# T4p1_fpc_adapter.net
KiCad netlist of a schematic drawn in EAGLE
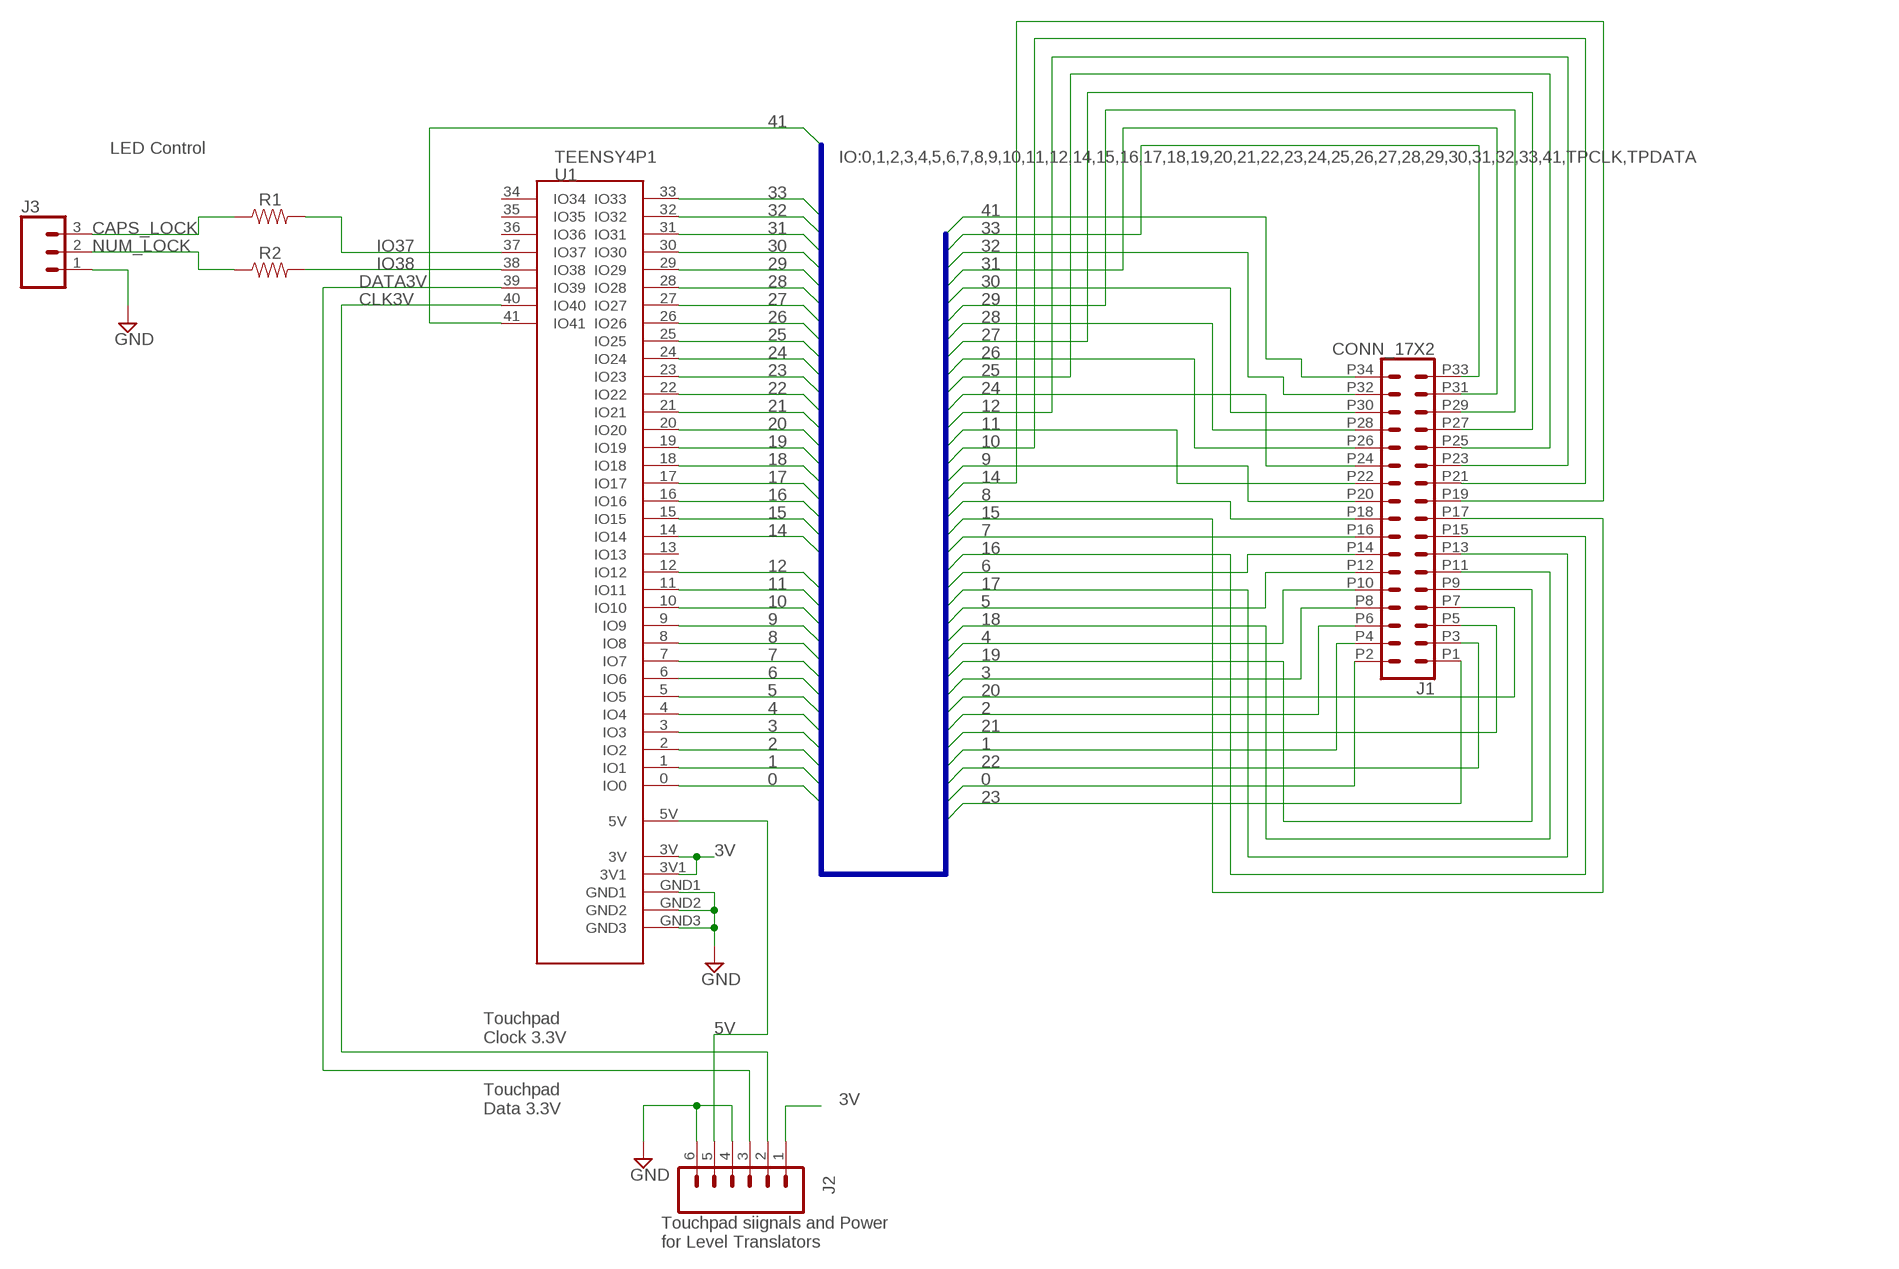
[diagram p0: schematic, sheet 1]

(export (version "E")
  (design (tool "Eeschema 10.0.6"))
  (components
    (comp (ref "J1")
      (value "CONN_17X2")
      (footprint "eagle-import:2X17")
      (libsource (lib "eagle-import") (part "CONN_17X2"))
    )
    (comp (ref "J2")
      (value "CONN_06NO_SILK_FEMALE_PTH")
      (footprint "eagle-import:1X06_NO_SILK")
      (libsource (lib "eagle-import") (part "CONN_06NO_SILK_FEMALE_PTH"))
    )
    (comp (ref "J3")
      (value "CONN_031X03_NO_SILK")
      (footprint "eagle-import:1X03_NO_SILK")
      (libsource (lib "eagle-import") (part "CONN_031X03_NO_SILK"))
    )
    (comp (ref "R1")
      (value "RESISTOR_AXIAL")
      (footprint "eagle-import:AXIAL-0.3")
      (libsource (lib "eagle-import") (part "RESISTOR_AXIAL"))
    )
    (comp (ref "R2")
      (value "RESISTOR_AXIAL")
      (footprint "eagle-import:AXIAL-0.3")
      (libsource (lib "eagle-import") (part "RESISTOR_AXIAL"))
    )
    (comp (ref "U1")
      (value "TEENSY4P1")
      (footprint "eagle-import:TEENSY4P1")
      (libsource (lib "eagle-import") (part "TEENSYP41"))
    )
  )
  (nets
    (net (code "4") (name "/0") (class "Default")
      (node (ref "J1") (pin "P2") (pinfunction "2_P2") (pintype "passive"))
      (node (ref "U1") (pin "0") (pinfunction "IO0_0") (pintype "bidirectional"))
    )
    (net (code "5") (name "/1") (class "Default")
      (node (ref "J1") (pin "P4") (pinfunction "4_P4") (pintype "passive"))
      (node (ref "U1") (pin "1") (pinfunction "IO1_1") (pintype "bidirectional"))
    )
    (net (code "6") (name "/2") (class "Default")
      (node (ref "J1") (pin "P6") (pinfunction "6_P6") (pintype "passive"))
      (node (ref "U1") (pin "2") (pinfunction "IO2_2") (pintype "bidirectional"))
    )
    (net (code "7") (name "/3") (class "Default")
      (node (ref "J1") (pin "P8") (pinfunction "8_P8") (pintype "passive"))
      (node (ref "U1") (pin "3") (pinfunction "IO3_3") (pintype "bidirectional"))
    )
    (net (code "8") (name "/3V") (class "Default")
      (node (ref "J2") (pin "1") (pinfunction "1_1") (pintype "passive"))
      (node (ref "U1") (pin "3V") (pinfunction "3V_3V") (pintype "bidirectional"))
      (node (ref "U1") (pin "3V1") (pinfunction "3V1_3V1") (pintype "bidirectional"))
    )
    (net (code "9") (name "/4") (class "Default")
      (node (ref "J1") (pin "P10") (pinfunction "10_P10") (pintype "passive"))
      (node (ref "U1") (pin "4") (pinfunction "IO4_4") (pintype "bidirectional"))
    )
    (net (code "10") (name "/5") (class "Default")
      (node (ref "J1") (pin "P12") (pinfunction "12_P12") (pintype "passive"))
      (node (ref "U1") (pin "5") (pinfunction "IO5_5") (pintype "bidirectional"))
    )
    (net (code "11") (name "/5V") (class "Default")
      (node (ref "J2") (pin "5") (pinfunction "5_5") (pintype "passive"))
      (node (ref "U1") (pin "5V") (pinfunction "5V_5V") (pintype "bidirectional"))
    )
    (net (code "12") (name "/6") (class "Default")
      (node (ref "J1") (pin "P14") (pinfunction "14_P14") (pintype "passive"))
      (node (ref "U1") (pin "6") (pinfunction "IO6_6") (pintype "bidirectional"))
    )
    (net (code "13") (name "/7") (class "Default")
      (node (ref "J1") (pin "P16") (pinfunction "16_P16") (pintype "passive"))
      (node (ref "U1") (pin "7") (pinfunction "IO7_7") (pintype "bidirectional"))
    )
    (net (code "14") (name "/8") (class "Default")
      (node (ref "J1") (pin "P18") (pinfunction "18_P18") (pintype "passive"))
      (node (ref "U1") (pin "8") (pinfunction "IO8_8") (pintype "bidirectional"))
    )
    (net (code "15") (name "/9") (class "Default")
      (node (ref "J1") (pin "P20") (pinfunction "20_P20") (pintype "passive"))
      (node (ref "U1") (pin "9") (pinfunction "IO9_9") (pintype "bidirectional"))
    )
    (net (code "16") (name "/10") (class "Default")
      (node (ref "J1") (pin "P21") (pinfunction "21_P21") (pintype "passive"))
      (node (ref "U1") (pin "10") (pinfunction "IO10_10") (pintype "bidirectional"))
    )
    (net (code "17") (name "/11") (class "Default")
      (node (ref "J1") (pin "P22") (pinfunction "22_P22") (pintype "passive"))
      (node (ref "U1") (pin "11") (pinfunction "IO11_11") (pintype "bidirectional"))
    )
    (net (code "18") (name "/12") (class "Default")
      (node (ref "J1") (pin "P23") (pinfunction "23_P23") (pintype "passive"))
      (node (ref "U1") (pin "12") (pinfunction "IO12_12") (pintype "bidirectional"))
    )
    (net (code "19") (name "/14") (class "Default")
      (node (ref "J1") (pin "P19") (pinfunction "19_P19") (pintype "passive"))
      (node (ref "U1") (pin "14") (pinfunction "IO14_14") (pintype "bidirectional"))
    )
    (net (code "20") (name "/15") (class "Default")
      (node (ref "J1") (pin "P17") (pinfunction "17_P17") (pintype "passive"))
      (node (ref "U1") (pin "15") (pinfunction "IO15_15") (pintype "bidirectional"))
    )
    (net (code "21") (name "/16") (class "Default")
      (node (ref "J1") (pin "P15") (pinfunction "15_P15") (pintype "passive"))
      (node (ref "U1") (pin "16") (pinfunction "IO16_16") (pintype "bidirectional"))
    )
    (net (code "22") (name "/17") (class "Default")
      (node (ref "J1") (pin "P13") (pinfunction "13_P13") (pintype "passive"))
      (node (ref "U1") (pin "17") (pinfunction "IO17_17") (pintype "bidirectional"))
    )
    (net (code "23") (name "/18") (class "Default")
      (node (ref "J1") (pin "P11") (pinfunction "11_P11") (pintype "passive"))
      (node (ref "U1") (pin "18") (pinfunction "IO18_18") (pintype "bidirectional"))
    )
    (net (code "24") (name "/19") (class "Default")
      (node (ref "J1") (pin "P9") (pinfunction "9_P9") (pintype "passive"))
      (node (ref "U1") (pin "19") (pinfunction "IO19_19") (pintype "bidirectional"))
    )
    (net (code "25") (name "/20") (class "Default")
      (node (ref "J1") (pin "P7") (pinfunction "7_P7") (pintype "passive"))
      (node (ref "U1") (pin "20") (pinfunction "IO20_20") (pintype "bidirectional"))
    )
    (net (code "26") (name "/21") (class "Default")
      (node (ref "J1") (pin "P5") (pinfunction "5_P5") (pintype "passive"))
      (node (ref "U1") (pin "21") (pinfunction "IO21_21") (pintype "bidirectional"))
    )
    (net (code "27") (name "/22") (class "Default")
      (node (ref "J1") (pin "P3") (pinfunction "3_P3") (pintype "passive"))
      (node (ref "U1") (pin "22") (pinfunction "IO22_22") (pintype "bidirectional"))
    )
    (net (code "28") (name "/23") (class "Default")
      (node (ref "J1") (pin "P1") (pinfunction "1_P1") (pintype "passive"))
      (node (ref "U1") (pin "23") (pinfunction "IO23_23") (pintype "bidirectional"))
    )
    (net (code "29") (name "/24") (class "Default")
      (node (ref "J1") (pin "P24") (pinfunction "24_P24") (pintype "passive"))
      (node (ref "U1") (pin "24") (pinfunction "IO24_24") (pintype "bidirectional"))
    )
    (net (code "30") (name "/25") (class "Default")
      (node (ref "J1") (pin "P25") (pinfunction "25_P25") (pintype "passive"))
      (node (ref "U1") (pin "25") (pinfunction "IO25_25") (pintype "bidirectional"))
    )
    (net (code "31") (name "/26") (class "Default")
      (node (ref "J1") (pin "P26") (pinfunction "26_P26") (pintype "passive"))
      (node (ref "U1") (pin "26") (pinfunction "IO26_26") (pintype "bidirectional"))
    )
    (net (code "32") (name "/27") (class "Default")
      (node (ref "J1") (pin "P27") (pinfunction "27_P27") (pintype "passive"))
      (node (ref "U1") (pin "27") (pinfunction "IO27_27") (pintype "bidirectional"))
    )
    (net (code "33") (name "/28") (class "Default")
      (node (ref "J1") (pin "P28") (pinfunction "28_P28") (pintype "passive"))
      (node (ref "U1") (pin "28") (pinfunction "IO28_28") (pintype "bidirectional"))
    )
    (net (code "34") (name "/29") (class "Default")
      (node (ref "J1") (pin "P29") (pinfunction "29_P29") (pintype "passive"))
      (node (ref "U1") (pin "29") (pinfunction "IO29_29") (pintype "bidirectional"))
    )
    (net (code "35") (name "/30") (class "Default")
      (node (ref "J1") (pin "P30") (pinfunction "30_P30") (pintype "passive"))
      (node (ref "U1") (pin "30") (pinfunction "IO30_30") (pintype "bidirectional"))
    )
    (net (code "36") (name "/31") (class "Default")
      (node (ref "J1") (pin "P31") (pinfunction "31_P31") (pintype "passive"))
      (node (ref "U1") (pin "31") (pinfunction "IO31_31") (pintype "bidirectional"))
    )
    (net (code "37") (name "/32") (class "Default")
      (node (ref "J1") (pin "P32") (pinfunction "32_P32") (pintype "passive"))
      (node (ref "U1") (pin "32") (pinfunction "IO32_32") (pintype "bidirectional"))
    )
    (net (code "38") (name "/33") (class "Default")
      (node (ref "J1") (pin "P33") (pinfunction "33_P33") (pintype "passive"))
      (node (ref "U1") (pin "33") (pinfunction "IO33_33") (pintype "bidirectional"))
    )
    (net (code "39") (name "/41") (class "Default")
      (node (ref "J1") (pin "P34") (pinfunction "34_P34") (pintype "passive"))
      (node (ref "U1") (pin "41") (pinfunction "IO41_41") (pintype "bidirectional"))
    )
    (net (code "40") (name "/CAPS_LOCK") (class "Default")
      (node (ref "J3") (pin "3") (pinfunction "3_3") (pintype "passive"))
      (node (ref "R1") (pin "P$1") (pinfunction "1_P$1") (pintype "passive"))
    )
    (net (code "41") (name "/CLK3V") (class "Default")
      (node (ref "J2") (pin "2") (pinfunction "2_2") (pintype "passive"))
      (node (ref "U1") (pin "40") (pinfunction "IO40_40") (pintype "bidirectional"))
    )
    (net (code "42") (name "/DATA3V") (class "Default")
      (node (ref "J2") (pin "3") (pinfunction "3_3") (pintype "passive"))
      (node (ref "U1") (pin "39") (pinfunction "IO39_39") (pintype "bidirectional"))
    )
    (net (code "43") (name "/IO37") (class "Default")
      (node (ref "R1") (pin "P$2") (pinfunction "2_P$2") (pintype "passive"))
      (node (ref "U1") (pin "37") (pinfunction "IO37_37") (pintype "bidirectional"))
    )
    (net (code "44") (name "/IO38") (class "Default")
      (node (ref "R2") (pin "P$2") (pinfunction "2_P$2") (pintype "passive"))
      (node (ref "U1") (pin "38") (pinfunction "IO38_38") (pintype "bidirectional"))
    )
    (net (code "45") (name "/NUM_LOCK") (class "Default")
      (node (ref "J3") (pin "2") (pinfunction "2_2") (pintype "passive"))
      (node (ref "R2") (pin "P$1") (pinfunction "1_P$1") (pintype "passive"))
    )
    (net (code "47") (name "GND") (class "Default")
      (node (ref "J2") (pin "4") (pinfunction "4_4") (pintype "passive"))
      (node (ref "J2") (pin "6") (pinfunction "6_6") (pintype "passive"))
      (node (ref "J3") (pin "1") (pinfunction "1_1") (pintype "passive"))
      (node (ref "U1") (pin "GND1") (pinfunction "GND1_GND1") (pintype "bidirectional"))
      (node (ref "U1") (pin "GND2") (pinfunction "GND2_GND2") (pintype "bidirectional"))
      (node (ref "U1") (pin "GND3") (pinfunction "GND3_GND3") (pintype "bidirectional"))
    )
    (net (code "48") (name "unconnected-(U1-IO13-Pad13)") (class "Default")
      (node (ref "U1") (pin "13") (pinfunction "IO13_13") (pintype "bidirectional"))
    )
    (net (code "49") (name "unconnected-(U1-IO34-Pad34)") (class "Default")
      (node (ref "U1") (pin "34") (pinfunction "IO34_34") (pintype "bidirectional"))
    )
    (net (code "50") (name "unconnected-(U1-IO35-Pad35)") (class "Default")
      (node (ref "U1") (pin "35") (pinfunction "IO35_35") (pintype "bidirectional"))
    )
    (net (code "51") (name "unconnected-(U1-IO36-Pad36)") (class "Default")
      (node (ref "U1") (pin "36") (pinfunction "IO36_36") (pintype "bidirectional"))
    )
  )
)
